# Keys10_1V0.net
KiCad netlist of a schematic drawn in EAGLE
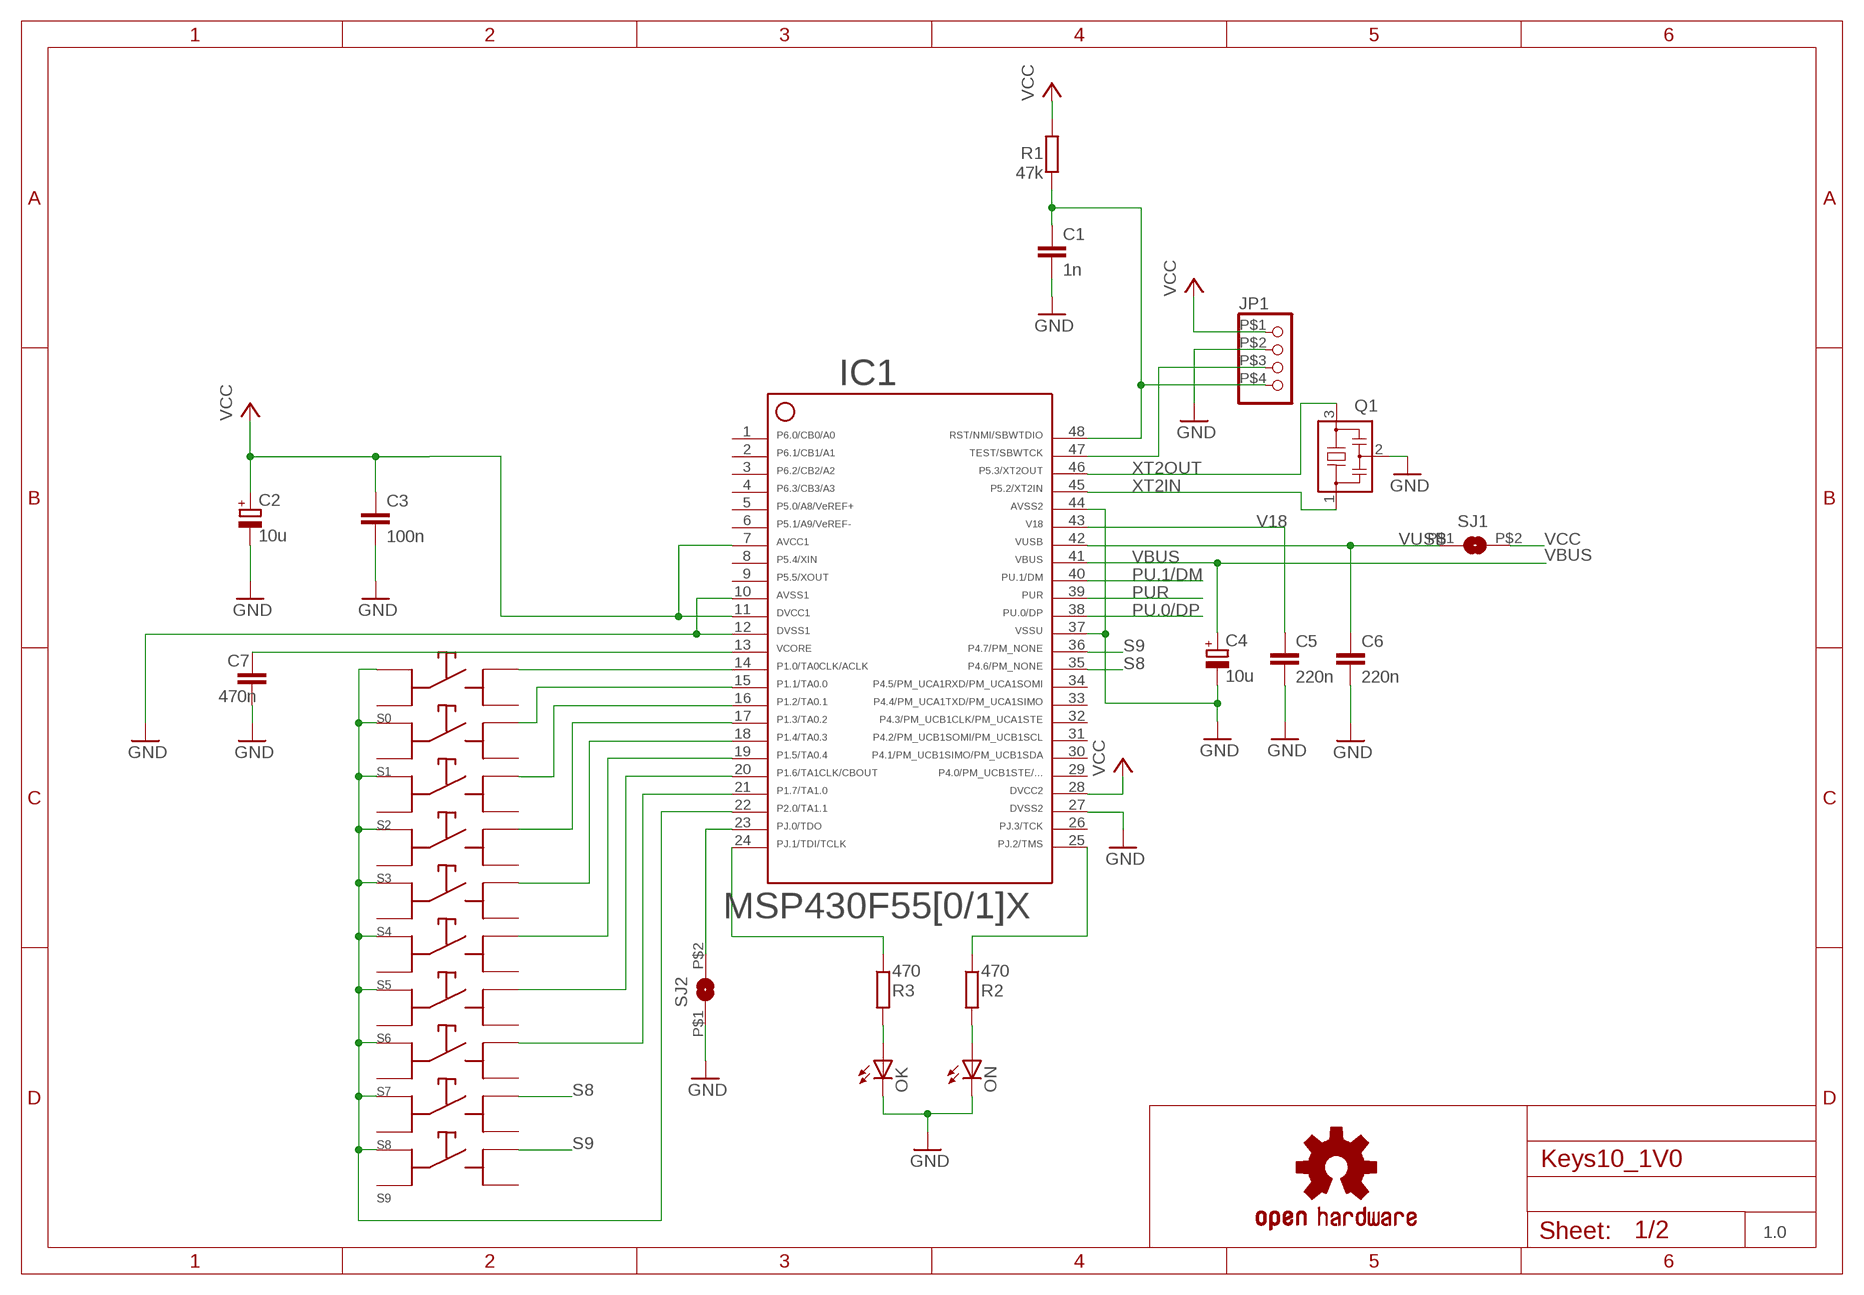
[diagram p0: schematic, sheet 1]
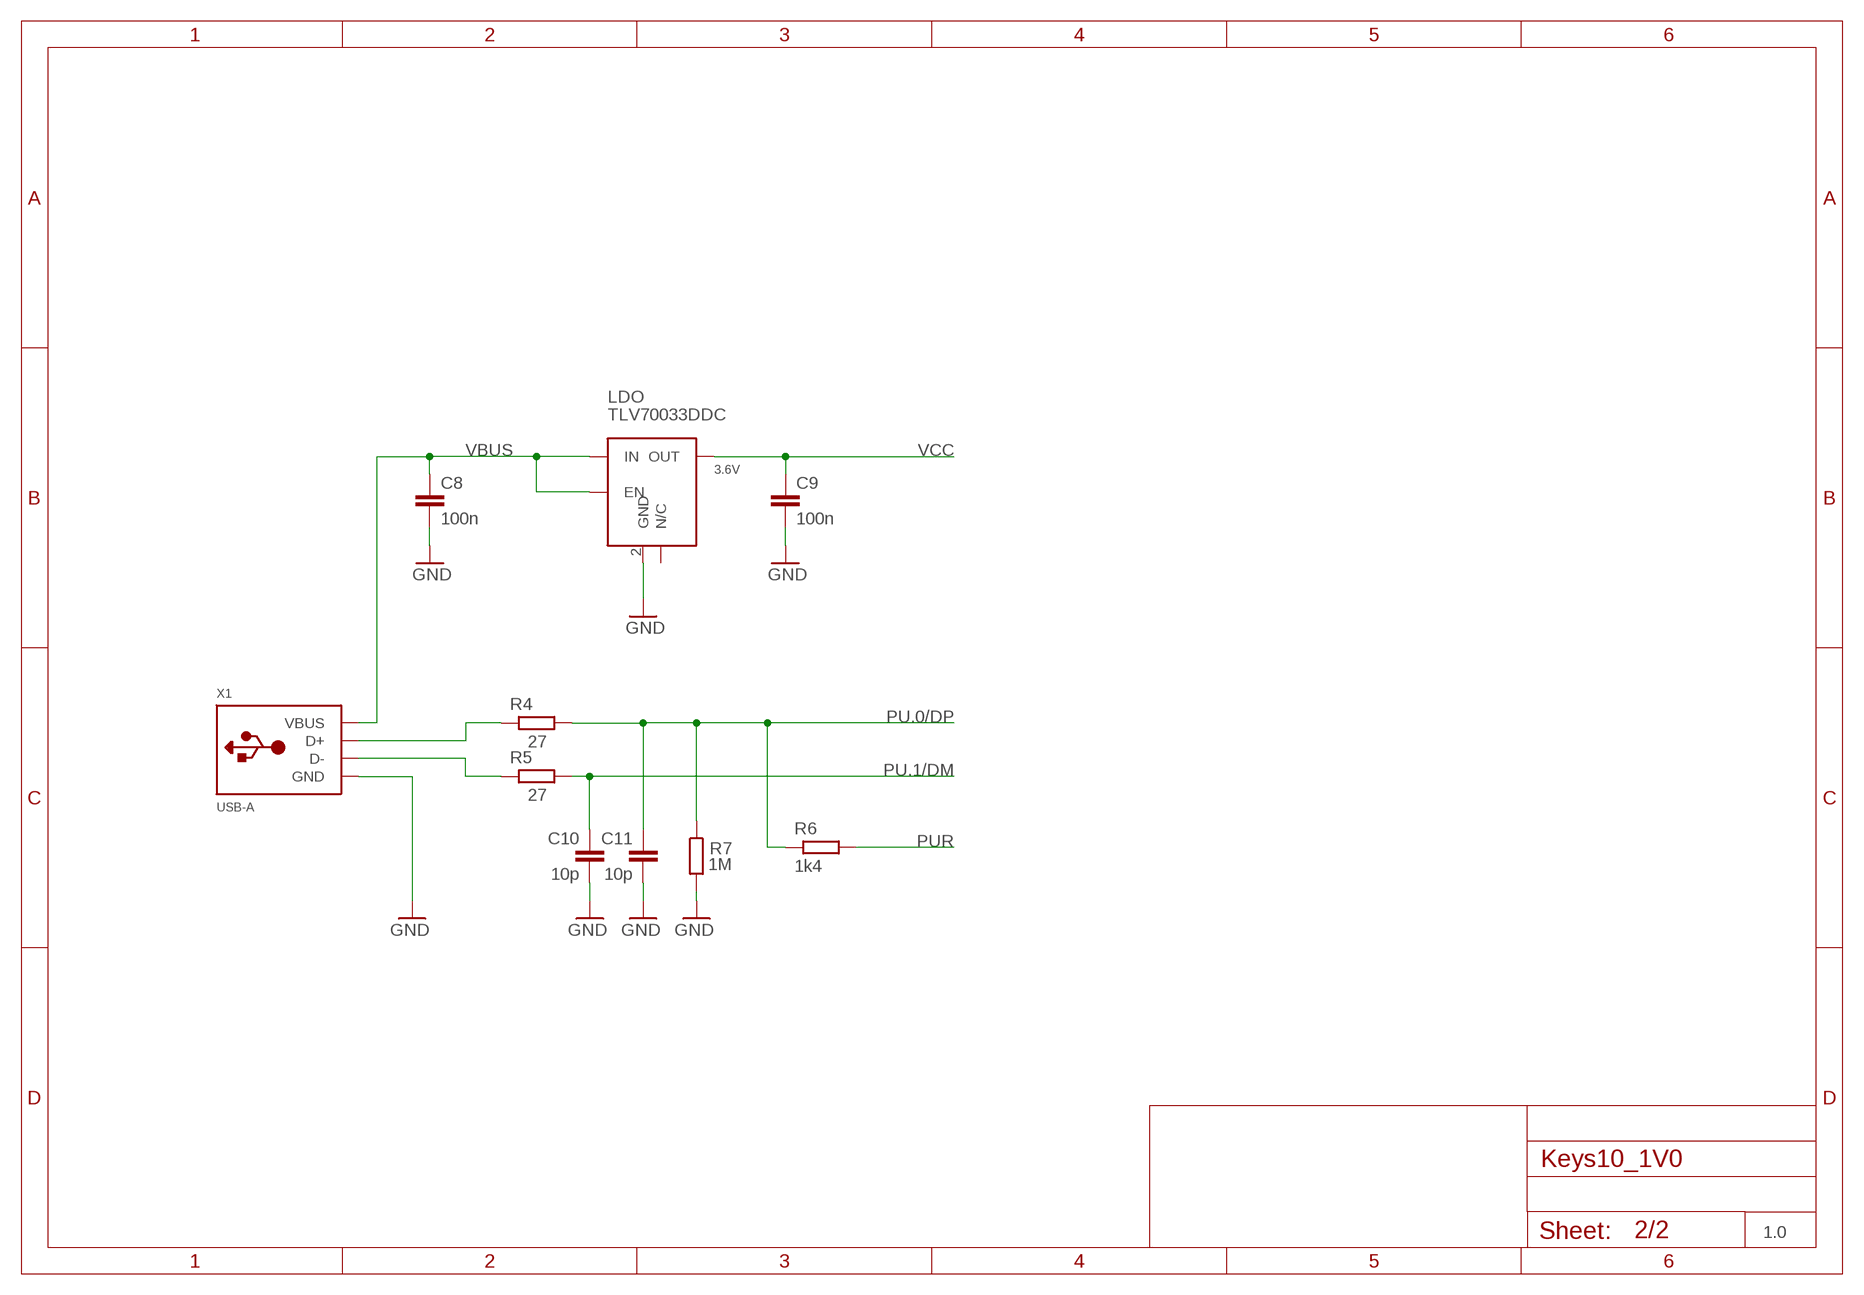
[diagram p1: schematic, sheet 2]

(export (version "E")
  (design (tool "Eeschema 10.0.6"))
  (components
    (comp (ref "C8")
      (value "100n")
      (footprint "eagle-import:C0805")
      (libsource (lib "eagle-import") (part "C-EUC0805"))
    )
    (comp (ref "C9")
      (value "100n")
      (footprint "eagle-import:C0805")
      (libsource (lib "eagle-import") (part "C-EUC0805"))
    )
    (comp (ref "C10")
      (value "10p")
      (footprint "eagle-import:C0805")
      (libsource (lib "eagle-import") (part "C-EUC0805"))
    )
    (comp (ref "C11")
      (value "10p")
      (footprint "eagle-import:C0805")
      (libsource (lib "eagle-import") (part "C-EUC0805"))
    )
    (comp (ref "LDO")
      (value "TLV70033DDC")
      (footprint "eagle-import:SOT23-5")
      (libsource (lib "eagle-import") (part "TLV700XXDDC"))
    )
    (comp (ref "R4")
      (value "27")
      (footprint "eagle-import:R0805")
      (libsource (lib "eagle-import") (part "R-EU_R0805"))
    )
    (comp (ref "R5")
      (value "27")
      (footprint "eagle-import:R0805")
      (libsource (lib "eagle-import") (part "R-EU_R0805"))
    )
    (comp (ref "R6")
      (value "1k4")
      (footprint "eagle-import:R0805")
      (libsource (lib "eagle-import") (part "R-EU_R0805"))
    )
    (comp (ref "R7")
      (value "1M")
      (footprint "eagle-import:R0805")
      (libsource (lib "eagle-import") (part "R-EU_R0805"))
    )
    (comp (ref "X1")
      (value "USB-A")
      (footprint "eagle-import:MOLEX_480371000")
      (libsource (lib "eagle-import") (part "USB-A"))
    )
    (comp (ref "C1")
      (value "1n")
      (footprint "eagle-import:C0805")
      (libsource (lib "eagle-import") (part "C-EUC0805"))
    )
    (comp (ref "C2")
      (value "10u")
      (footprint "eagle-import:R_2012-12R")
      (libsource (lib "eagle-import") (part "CPOL-EUR/2012-12R"))
    )
    (comp (ref "C3")
      (value "100n")
      (footprint "eagle-import:C0805")
      (libsource (lib "eagle-import") (part "C-EUC0805"))
    )
    (comp (ref "C4")
      (value "10u")
      (footprint "eagle-import:R_2012-12R")
      (libsource (lib "eagle-import") (part "CPOL-EUR/2012-12R"))
    )
    (comp (ref "C5")
      (value "220n")
      (footprint "eagle-import:C0805")
      (libsource (lib "eagle-import") (part "C-EUC0805"))
    )
    (comp (ref "C6")
      (value "220n")
      (footprint "eagle-import:C0805")
      (libsource (lib "eagle-import") (part "C-EUC0805"))
    )
    (comp (ref "C7")
      (value "470n")
      (footprint "eagle-import:C0805")
      (libsource (lib "eagle-import") (part "C-EUC0805"))
    )
    (comp (ref "IC1")
      (value "F5509")
      (footprint "eagle-import:PT48")
      (libsource (lib "eagle-import") (part "F55[0/1]X---PT48"))
    )
    (comp (ref "JP1")
      (value "PINHD-1X4S")
      (footprint "eagle-import:1X04S")
      (libsource (lib "eagle-import") (part "PINHD-1X4S"))
    )
    (comp (ref "OK")
      (value "LEDCHIPLED_0805")
      (footprint "eagle-import:CHIPLED_0805")
      (libsource (lib "eagle-import") (part "LEDCHIPLED_0805"))
    )
    (comp (ref "ON")
      (value "LEDCHIPLED_0805")
      (footprint "eagle-import:CHIPLED_0805")
      (libsource (lib "eagle-import") (part "LEDCHIPLED_0805"))
    )
    (comp (ref "Q1")
      (value "PIEZO_CSTCR4M00G15L99")
      (footprint "eagle-import:CSTCR6M")
      (fields (field (name "MPN") "CSTCR6M00G53-R0"))
      (libsource (lib "eagle-import") (part "CSTCR6M00G53Z"))
    )
    (comp (ref "R1")
      (value "47k")
      (footprint "eagle-import:R0805")
      (libsource (lib "eagle-import") (part "R-EU_R0805"))
    )
    (comp (ref "R2")
      (value "470")
      (footprint "eagle-import:R0805")
      (libsource (lib "eagle-import") (part "R-EU_R0805"))
    )
    (comp (ref "R3")
      (value "470")
      (footprint "eagle-import:R0805")
      (libsource (lib "eagle-import") (part "R-EU_R0805"))
    )
    (comp (ref "S0")
      (value "HDKJ")
      (footprint "eagle-import:HDKJ")
      (libsource (lib "eagle-import") (part "HDKJ"))
    )
    (comp (ref "S1")
      (value "HDKJ")
      (footprint "eagle-import:HDKJ")
      (libsource (lib "eagle-import") (part "HDKJ"))
    )
    (comp (ref "S2")
      (value "HDKJ")
      (footprint "eagle-import:HDKJ")
      (libsource (lib "eagle-import") (part "HDKJ"))
    )
    (comp (ref "S3")
      (value "HDKJ")
      (footprint "eagle-import:HDKJ")
      (libsource (lib "eagle-import") (part "HDKJ"))
    )
    (comp (ref "S4")
      (value "HDKJ")
      (footprint "eagle-import:HDKJ")
      (libsource (lib "eagle-import") (part "HDKJ"))
    )
    (comp (ref "S5")
      (value "HDKJ")
      (footprint "eagle-import:HDKJ")
      (libsource (lib "eagle-import") (part "HDKJ"))
    )
    (comp (ref "S6")
      (value "HDKJ")
      (footprint "eagle-import:HDKJ")
      (libsource (lib "eagle-import") (part "HDKJ"))
    )
    (comp (ref "S7")
      (value "HDKJ")
      (footprint "eagle-import:HDKJ")
      (libsource (lib "eagle-import") (part "HDKJ"))
    )
    (comp (ref "S8")
      (value "HDKJ")
      (footprint "eagle-import:HDKJ")
      (libsource (lib "eagle-import") (part "HDKJ"))
    )
    (comp (ref "S9")
      (value "HDKJ")
      (footprint "eagle-import:HDKJ")
      (libsource (lib "eagle-import") (part "HDKJ"))
    )
    (comp (ref "SJ1")
      (value "SJM")
      (footprint "eagle-import:SJ_M")
      (libsource (lib "eagle-import") (part "SJM"))
    )
    (comp (ref "SJ2")
      (value "SJM")
      (footprint "eagle-import:SJ_M")
      (libsource (lib "eagle-import") (part "SJM"))
    )
    (comp (ref "U$1")
      (value "OSHW_LOGO_SYMS")
      (footprint "eagle-import:OSHW_LOGO_SMALL_SYM")
      (libsource (lib "eagle-import") (part "OSHW_LOGO_SYMS"))
    )
  )
  (nets
    (net (code "1") (name "GND") (class "Default")
      (node (ref "C1") (pin "2") (pinfunction "2_2") (pintype "passive"))
      (node (ref "C10") (pin "2") (pinfunction "2_2") (pintype "passive"))
      (node (ref "C11") (pin "2") (pinfunction "2_2") (pintype "passive"))
      (node (ref "C2") (pin "-") (pinfunction "-_-") (pintype "passive"))
      (node (ref "C3") (pin "2") (pinfunction "2_2") (pintype "passive"))
      (node (ref "C4") (pin "-") (pinfunction "-_-") (pintype "passive"))
      (node (ref "C5") (pin "2") (pinfunction "2_2") (pintype "passive"))
      (node (ref "C6") (pin "2") (pinfunction "2_2") (pintype "passive"))
      (node (ref "C7") (pin "2") (pinfunction "2_2") (pintype "passive"))
      (node (ref "C8") (pin "2") (pinfunction "2_2") (pintype "passive"))
      (node (ref "C9") (pin "2") (pinfunction "2_2") (pintype "passive"))
      (node (ref "IC1") (pin "10") (pinfunction "10_10") (pintype "power_in"))
      (node (ref "IC1") (pin "12") (pinfunction "12_12") (pintype "power_in"))
      (node (ref "IC1") (pin "27") (pinfunction "27_27") (pintype "power_in"))
      (node (ref "IC1") (pin "37") (pinfunction "37_37") (pintype "power_in"))
      (node (ref "IC1") (pin "44") (pinfunction "44_44") (pintype "power_in"))
      (node (ref "JP1") (pin "P$2") (pinfunction "2_P$2") (pintype "passive"))
      (node (ref "LDO") (pin "2") (pinfunction "GND_2") (pintype "bidirectional"))
      (node (ref "OK") (pin "C") (pinfunction "C_C") (pintype "passive"))
      (node (ref "ON") (pin "C") (pinfunction "C_C") (pintype "passive"))
      (node (ref "Q1") (pin "2") (pinfunction "2_2") (pintype "passive"))
      (node (ref "R7") (pin "2") (pinfunction "2_2") (pintype "passive"))
      (node (ref "SJ2") (pin "P$1") (pinfunction "1_P$1") (pintype "passive"))
      (node (ref "X1") (pin "4") (pinfunction "GND_4") (pintype "power_in"))
      (node (ref "X1") (pin "M1") (pinfunction "GND_M1") (pintype "power_in"))
      (node (ref "X1") (pin "M2") (pinfunction "GND_M2") (pintype "power_in"))
    )
    (net (code "2") (name "Net-(C7-Pad1)") (class "Default")
      (node (ref "C7") (pin "1") (pinfunction "1_1") (pintype "passive"))
      (node (ref "IC1") (pin "13") (pinfunction "13_13") (pintype "power_in"))
    )
    (net (code "3") (name "Net-(IC1-Pad22)") (class "Default")
      (node (ref "IC1") (pin "22") (pinfunction "22_22") (pintype "bidirectional"))
      (node (ref "S0") (pin "IN1") (pinfunction "IN1_IN1") (pintype "bidirectional"))
      (node (ref "S1") (pin "IN1") (pinfunction "IN1_IN1") (pintype "bidirectional"))
      (node (ref "S2") (pin "IN1") (pinfunction "IN1_IN1") (pintype "bidirectional"))
      (node (ref "S3") (pin "IN1") (pinfunction "IN1_IN1") (pintype "bidirectional"))
      (node (ref "S4") (pin "IN1") (pinfunction "IN1_IN1") (pintype "bidirectional"))
      (node (ref "S5") (pin "IN1") (pinfunction "IN1_IN1") (pintype "bidirectional"))
      (node (ref "S6") (pin "IN1") (pinfunction "IN1_IN1") (pintype "bidirectional"))
      (node (ref "S7") (pin "IN1") (pinfunction "IN1_IN1") (pintype "bidirectional"))
      (node (ref "S8") (pin "IN1") (pinfunction "IN1_IN1") (pintype "bidirectional"))
      (node (ref "S9") (pin "IN1") (pinfunction "IN1_IN1") (pintype "bidirectional"))
    )
    (net (code "4") (name "Net-(IC1-Pad24)") (class "Default")
      (node (ref "IC1") (pin "24") (pinfunction "24_24") (pintype "bidirectional"))
      (node (ref "R3") (pin "1") (pinfunction "1_1") (pintype "passive"))
    )
    (net (code "5") (name "Net-(IC1-Pad25)") (class "Default")
      (node (ref "IC1") (pin "25") (pinfunction "25_25") (pintype "bidirectional"))
      (node (ref "R2") (pin "1") (pinfunction "1_1") (pintype "passive"))
    )
    (net (code "6") (name "Net-(JP1-3)") (class "Default")
      (node (ref "IC1") (pin "47") (pinfunction "47_47") (pintype "input"))
      (node (ref "JP1") (pin "P$3") (pinfunction "3_P$3") (pintype "passive"))
    )
    (net (code "7") (name "Net-(JP1-4)") (class "Default")
      (node (ref "C1") (pin "1") (pinfunction "1_1") (pintype "passive"))
      (node (ref "IC1") (pin "48") (pinfunction "48_48") (pintype "bidirectional"))
      (node (ref "JP1") (pin "P$4") (pinfunction "4_P$4") (pintype "passive"))
      (node (ref "R1") (pin "1") (pinfunction "1_1") (pintype "passive"))
    )
    (net (code "8") (name "Net-(OK-PadA)") (class "Default")
      (node (ref "OK") (pin "A") (pinfunction "A_A") (pintype "passive"))
      (node (ref "R3") (pin "2") (pinfunction "2_2") (pintype "passive"))
    )
    (net (code "9") (name "Net-(ON-PadA)") (class "Default")
      (node (ref "ON") (pin "A") (pinfunction "A_A") (pintype "passive"))
      (node (ref "R2") (pin "2") (pinfunction "2_2") (pintype "passive"))
    )
    (net (code "10") (name "Net-(S0-OUT1)") (class "Default")
      (node (ref "IC1") (pin "14") (pinfunction "14_14") (pintype "bidirectional"))
      (node (ref "S0") (pin "OU1") (pinfunction "OUT1_OU1") (pintype "bidirectional"))
    )
    (net (code "11") (name "Net-(S1-OUT1)") (class "Default")
      (node (ref "IC1") (pin "15") (pinfunction "15_15") (pintype "bidirectional"))
      (node (ref "S1") (pin "OU1") (pinfunction "OUT1_OU1") (pintype "bidirectional"))
    )
    (net (code "12") (name "Net-(S2-OUT1)") (class "Default")
      (node (ref "IC1") (pin "16") (pinfunction "16_16") (pintype "bidirectional"))
      (node (ref "S2") (pin "OU1") (pinfunction "OUT1_OU1") (pintype "bidirectional"))
    )
    (net (code "13") (name "Net-(S3-OUT1)") (class "Default")
      (node (ref "IC1") (pin "17") (pinfunction "17_17") (pintype "bidirectional"))
      (node (ref "S3") (pin "OU1") (pinfunction "OUT1_OU1") (pintype "bidirectional"))
    )
    (net (code "14") (name "Net-(S4-OUT1)") (class "Default")
      (node (ref "IC1") (pin "18") (pinfunction "18_18") (pintype "bidirectional"))
      (node (ref "S4") (pin "OU1") (pinfunction "OUT1_OU1") (pintype "bidirectional"))
    )
    (net (code "15") (name "Net-(S5-OUT1)") (class "Default")
      (node (ref "IC1") (pin "19") (pinfunction "19_19") (pintype "bidirectional"))
      (node (ref "S5") (pin "OU1") (pinfunction "OUT1_OU1") (pintype "bidirectional"))
    )
    (net (code "16") (name "Net-(S6-OUT1)") (class "Default")
      (node (ref "IC1") (pin "20") (pinfunction "20_20") (pintype "bidirectional"))
      (node (ref "S6") (pin "OU1") (pinfunction "OUT1_OU1") (pintype "bidirectional"))
    )
    (net (code "17") (name "Net-(S7-OUT1)") (class "Default")
      (node (ref "IC1") (pin "21") (pinfunction "21_21") (pintype "bidirectional"))
      (node (ref "S7") (pin "OU1") (pinfunction "OUT1_OU1") (pintype "bidirectional"))
    )
    (net (code "18") (name "Net-(SJ2-2)") (class "Default")
      (node (ref "IC1") (pin "23") (pinfunction "23_23") (pintype "bidirectional"))
      (node (ref "SJ2") (pin "P$2") (pinfunction "2_P$2") (pintype "passive"))
    )
    (net (code "19") (name "Net-(X1-D+)") (class "Default")
      (node (ref "R4") (pin "1") (pinfunction "1_1") (pintype "passive"))
      (node (ref "X1") (pin "3") (pinfunction "D+_3") (pintype "bidirectional"))
    )
    (net (code "20") (name "Net-(X1-D-)") (class "Default")
      (node (ref "R5") (pin "1") (pinfunction "1_1") (pintype "passive"))
      (node (ref "X1") (pin "2") (pinfunction "D-_2") (pintype "bidirectional"))
    )
    (net (code "21") (name "PU.0{slash}DP") (class "Default")
      (node (ref "C11") (pin "1") (pinfunction "1_1") (pintype "passive"))
      (node (ref "IC1") (pin "38") (pinfunction "38_38") (pintype "bidirectional"))
      (node (ref "R4") (pin "2") (pinfunction "2_2") (pintype "passive"))
      (node (ref "R6") (pin "1") (pinfunction "1_1") (pintype "passive"))
      (node (ref "R7") (pin "1") (pinfunction "1_1") (pintype "passive"))
    )
    (net (code "22") (name "PU.1{slash}DM") (class "Default")
      (node (ref "C10") (pin "1") (pinfunction "1_1") (pintype "passive"))
      (node (ref "IC1") (pin "40") (pinfunction "40_40") (pintype "bidirectional"))
      (node (ref "R5") (pin "2") (pinfunction "2_2") (pintype "passive"))
    )
    (net (code "23") (name "PUR") (class "Default")
      (node (ref "IC1") (pin "39") (pinfunction "39_39") (pintype "bidirectional"))
      (node (ref "R6") (pin "2") (pinfunction "2_2") (pintype "passive"))
    )
    (net (code "24") (name "S8") (class "Default")
      (node (ref "IC1") (pin "35") (pinfunction "35_35") (pintype "bidirectional"))
      (node (ref "S8") (pin "OU1") (pinfunction "OUT1_OU1") (pintype "bidirectional"))
    )
    (net (code "25") (name "S9") (class "Default")
      (node (ref "IC1") (pin "36") (pinfunction "36_36") (pintype "bidirectional"))
      (node (ref "S9") (pin "OU1") (pinfunction "OUT1_OU1") (pintype "bidirectional"))
    )
    (net (code "26") (name "V18") (class "Default")
      (node (ref "C5") (pin "1") (pinfunction "1_1") (pintype "passive"))
      (node (ref "IC1") (pin "43") (pinfunction "43_43") (pintype "power_in"))
    )
    (net (code "27") (name "VBUS") (class "Default")
      (node (ref "C4") (pin "+") (pinfunction "+_+") (pintype "passive"))
      (node (ref "C8") (pin "1") (pinfunction "1_1") (pintype "passive"))
      (node (ref "IC1") (pin "41") (pinfunction "41_41") (pintype "power_in"))
      (node (ref "LDO") (pin "1") (pinfunction "IN_1") (pintype "bidirectional"))
      (node (ref "LDO") (pin "3") (pinfunction "EN_3") (pintype "bidirectional"))
      (node (ref "X1") (pin "1") (pinfunction "VBUS_1") (pintype "power_in"))
    )
    (net (code "28") (name "VCC") (class "Default")
      (node (ref "C2") (pin "+") (pinfunction "+_+") (pintype "passive"))
      (node (ref "C3") (pin "1") (pinfunction "1_1") (pintype "passive"))
      (node (ref "C9") (pin "1") (pinfunction "1_1") (pintype "passive"))
      (node (ref "IC1") (pin "11") (pinfunction "11_11") (pintype "power_in"))
      (node (ref "IC1") (pin "28") (pinfunction "28_28") (pintype "power_in"))
      (node (ref "IC1") (pin "7") (pinfunction "7_7") (pintype "power_in"))
      (node (ref "JP1") (pin "P$1") (pinfunction "1_P$1") (pintype "passive"))
      (node (ref "LDO") (pin "5") (pinfunction "OUT_5") (pintype "bidirectional"))
      (node (ref "R1") (pin "2") (pinfunction "2_2") (pintype "passive"))
      (node (ref "SJ1") (pin "P$2") (pinfunction "2_P$2") (pintype "passive"))
    )
    (net (code "29") (name "VUSB") (class "Default")
      (node (ref "C6") (pin "1") (pinfunction "1_1") (pintype "passive"))
      (node (ref "IC1") (pin "42") (pinfunction "42_42") (pintype "power_in"))
      (node (ref "SJ1") (pin "P$1") (pinfunction "1_P$1") (pintype "passive"))
    )
    (net (code "30") (name "XT2IN") (class "Default")
      (node (ref "IC1") (pin "45") (pinfunction "45_45") (pintype "bidirectional"))
      (node (ref "Q1") (pin "1") (pinfunction "1_1") (pintype "passive"))
    )
    (net (code "31") (name "XT2OUT") (class "Default")
      (node (ref "IC1") (pin "46") (pinfunction "46_46") (pintype "power_in"))
      (node (ref "Q1") (pin "3") (pinfunction "3_3") (pintype "passive"))
    )
    (net (code "32") (name "unconnected-(IC1-Pad1)") (class "Default")
      (node (ref "IC1") (pin "1") (pinfunction "1_1") (pintype "bidirectional"))
    )
    (net (code "33") (name "unconnected-(IC1-Pad2)") (class "Default")
      (node (ref "IC1") (pin "2") (pinfunction "2_2") (pintype "bidirectional"))
    )
    (net (code "34") (name "unconnected-(IC1-Pad3)") (class "Default")
      (node (ref "IC1") (pin "3") (pinfunction "3_3") (pintype "bidirectional"))
    )
    (net (code "35") (name "unconnected-(IC1-Pad4)") (class "Default")
      (node (ref "IC1") (pin "4") (pinfunction "4_4") (pintype "bidirectional"))
    )
    (net (code "36") (name "unconnected-(IC1-Pad5)") (class "Default")
      (node (ref "IC1") (pin "5") (pinfunction "5_5") (pintype "bidirectional"))
    )
    (net (code "37") (name "unconnected-(IC1-Pad6)") (class "Default")
      (node (ref "IC1") (pin "6") (pinfunction "6_6") (pintype "bidirectional"))
    )
    (net (code "38") (name "unconnected-(IC1-Pad8)") (class "Default")
      (node (ref "IC1") (pin "8") (pinfunction "8_8") (pintype "bidirectional"))
    )
    (net (code "39") (name "unconnected-(IC1-Pad9)") (class "Default")
      (node (ref "IC1") (pin "9") (pinfunction "9_9") (pintype "bidirectional"))
    )
    (net (code "40") (name "unconnected-(IC1-Pad26)") (class "Default")
      (node (ref "IC1") (pin "26") (pinfunction "26_26") (pintype "bidirectional"))
    )
    (net (code "41") (name "unconnected-(IC1-Pad29)") (class "Default")
      (node (ref "IC1") (pin "29") (pinfunction "29_29") (pintype "bidirectional"))
    )
    (net (code "42") (name "unconnected-(IC1-Pad30)") (class "Default")
      (node (ref "IC1") (pin "30") (pinfunction "30_30") (pintype "bidirectional"))
    )
    (net (code "43") (name "unconnected-(IC1-Pad31)") (class "Default")
      (node (ref "IC1") (pin "31") (pinfunction "31_31") (pintype "bidirectional"))
    )
    (net (code "44") (name "unconnected-(IC1-Pad32)") (class "Default")
      (node (ref "IC1") (pin "32") (pinfunction "32_32") (pintype "bidirectional"))
    )
    (net (code "45") (name "unconnected-(IC1-Pad33)") (class "Default")
      (node (ref "IC1") (pin "33") (pinfunction "33_33") (pintype "bidirectional"))
    )
    (net (code "46") (name "unconnected-(IC1-Pad34)") (class "Default")
      (node (ref "IC1") (pin "34") (pinfunction "34_34") (pintype "bidirectional"))
    )
    (net (code "47") (name "unconnected-(LDO-N{slash}C-Pad4)") (class "Default")
      (node (ref "LDO") (pin "4") (pinfunction "N/C_4") (pintype "bidirectional"))
    )
    (net (code "48") (name "unconnected-(S0-PadIN2)") (class "Default")
      (node (ref "S0") (pin "IN2") (pinfunction "IN2_IN2") (pintype "bidirectional"))
    )
    (net (code "49") (name "unconnected-(S0-PadOUT2)") (class "Default")
      (node (ref "S0") (pin "OUT2") (pinfunction "OUT2_OUT2") (pintype "bidirectional"))
    )
    (net (code "50") (name "unconnected-(S1-PadIN2)") (class "Default")
      (node (ref "S1") (pin "IN2") (pinfunction "IN2_IN2") (pintype "bidirectional"))
    )
    (net (code "51") (name "unconnected-(S1-PadOUT2)") (class "Default")
      (node (ref "S1") (pin "OUT2") (pinfunction "OUT2_OUT2") (pintype "bidirectional"))
    )
    (net (code "52") (name "unconnected-(S2-PadIN2)") (class "Default")
      (node (ref "S2") (pin "IN2") (pinfunction "IN2_IN2") (pintype "bidirectional"))
    )
    (net (code "53") (name "unconnected-(S2-PadOUT2)") (class "Default")
      (node (ref "S2") (pin "OUT2") (pinfunction "OUT2_OUT2") (pintype "bidirectional"))
    )
    (net (code "54") (name "unconnected-(S3-PadIN2)") (class "Default")
      (node (ref "S3") (pin "IN2") (pinfunction "IN2_IN2") (pintype "bidirectional"))
    )
    (net (code "55") (name "unconnected-(S3-PadOUT2)") (class "Default")
      (node (ref "S3") (pin "OUT2") (pinfunction "OUT2_OUT2") (pintype "bidirectional"))
    )
    (net (code "56") (name "unconnected-(S4-PadIN2)") (class "Default")
      (node (ref "S4") (pin "IN2") (pinfunction "IN2_IN2") (pintype "bidirectional"))
    )
    (net (code "57") (name "unconnected-(S4-PadOUT2)") (class "Default")
      (node (ref "S4") (pin "OUT2") (pinfunction "OUT2_OUT2") (pintype "bidirectional"))
    )
    (net (code "58") (name "unconnected-(S5-PadIN2)") (class "Default")
      (node (ref "S5") (pin "IN2") (pinfunction "IN2_IN2") (pintype "bidirectional"))
    )
    (net (code "59") (name "unconnected-(S5-PadOUT2)") (class "Default")
      (node (ref "S5") (pin "OUT2") (pinfunction "OUT2_OUT2") (pintype "bidirectional"))
    )
    (net (code "60") (name "unconnected-(S6-PadIN2)") (class "Default")
      (node (ref "S6") (pin "IN2") (pinfunction "IN2_IN2") (pintype "bidirectional"))
    )
    (net (code "61") (name "unconnected-(S6-PadOUT2)") (class "Default")
      (node (ref "S6") (pin "OUT2") (pinfunction "OUT2_OUT2") (pintype "bidirectional"))
    )
    (net (code "62") (name "unconnected-(S7-PadIN2)") (class "Default")
      (node (ref "S7") (pin "IN2") (pinfunction "IN2_IN2") (pintype "bidirectional"))
    )
    (net (code "63") (name "unconnected-(S7-PadOUT2)") (class "Default")
      (node (ref "S7") (pin "OUT2") (pinfunction "OUT2_OUT2") (pintype "bidirectional"))
    )
    (net (code "64") (name "unconnected-(S8-PadIN2)") (class "Default")
      (node (ref "S8") (pin "IN2") (pinfunction "IN2_IN2") (pintype "bidirectional"))
    )
    (net (code "65") (name "unconnected-(S8-PadOUT2)") (class "Default")
      (node (ref "S8") (pin "OUT2") (pinfunction "OUT2_OUT2") (pintype "bidirectional"))
    )
    (net (code "66") (name "unconnected-(S9-PadIN2)") (class "Default")
      (node (ref "S9") (pin "IN2") (pinfunction "IN2_IN2") (pintype "bidirectional"))
    )
    (net (code "67") (name "unconnected-(S9-PadOUT2)") (class "Default")
      (node (ref "S9") (pin "OUT2") (pinfunction "OUT2_OUT2") (pintype "bidirectional"))
    )
  )
)
